# DCDC_RPI.net
KiCad netlist of a schematic drawn in Altium Designer
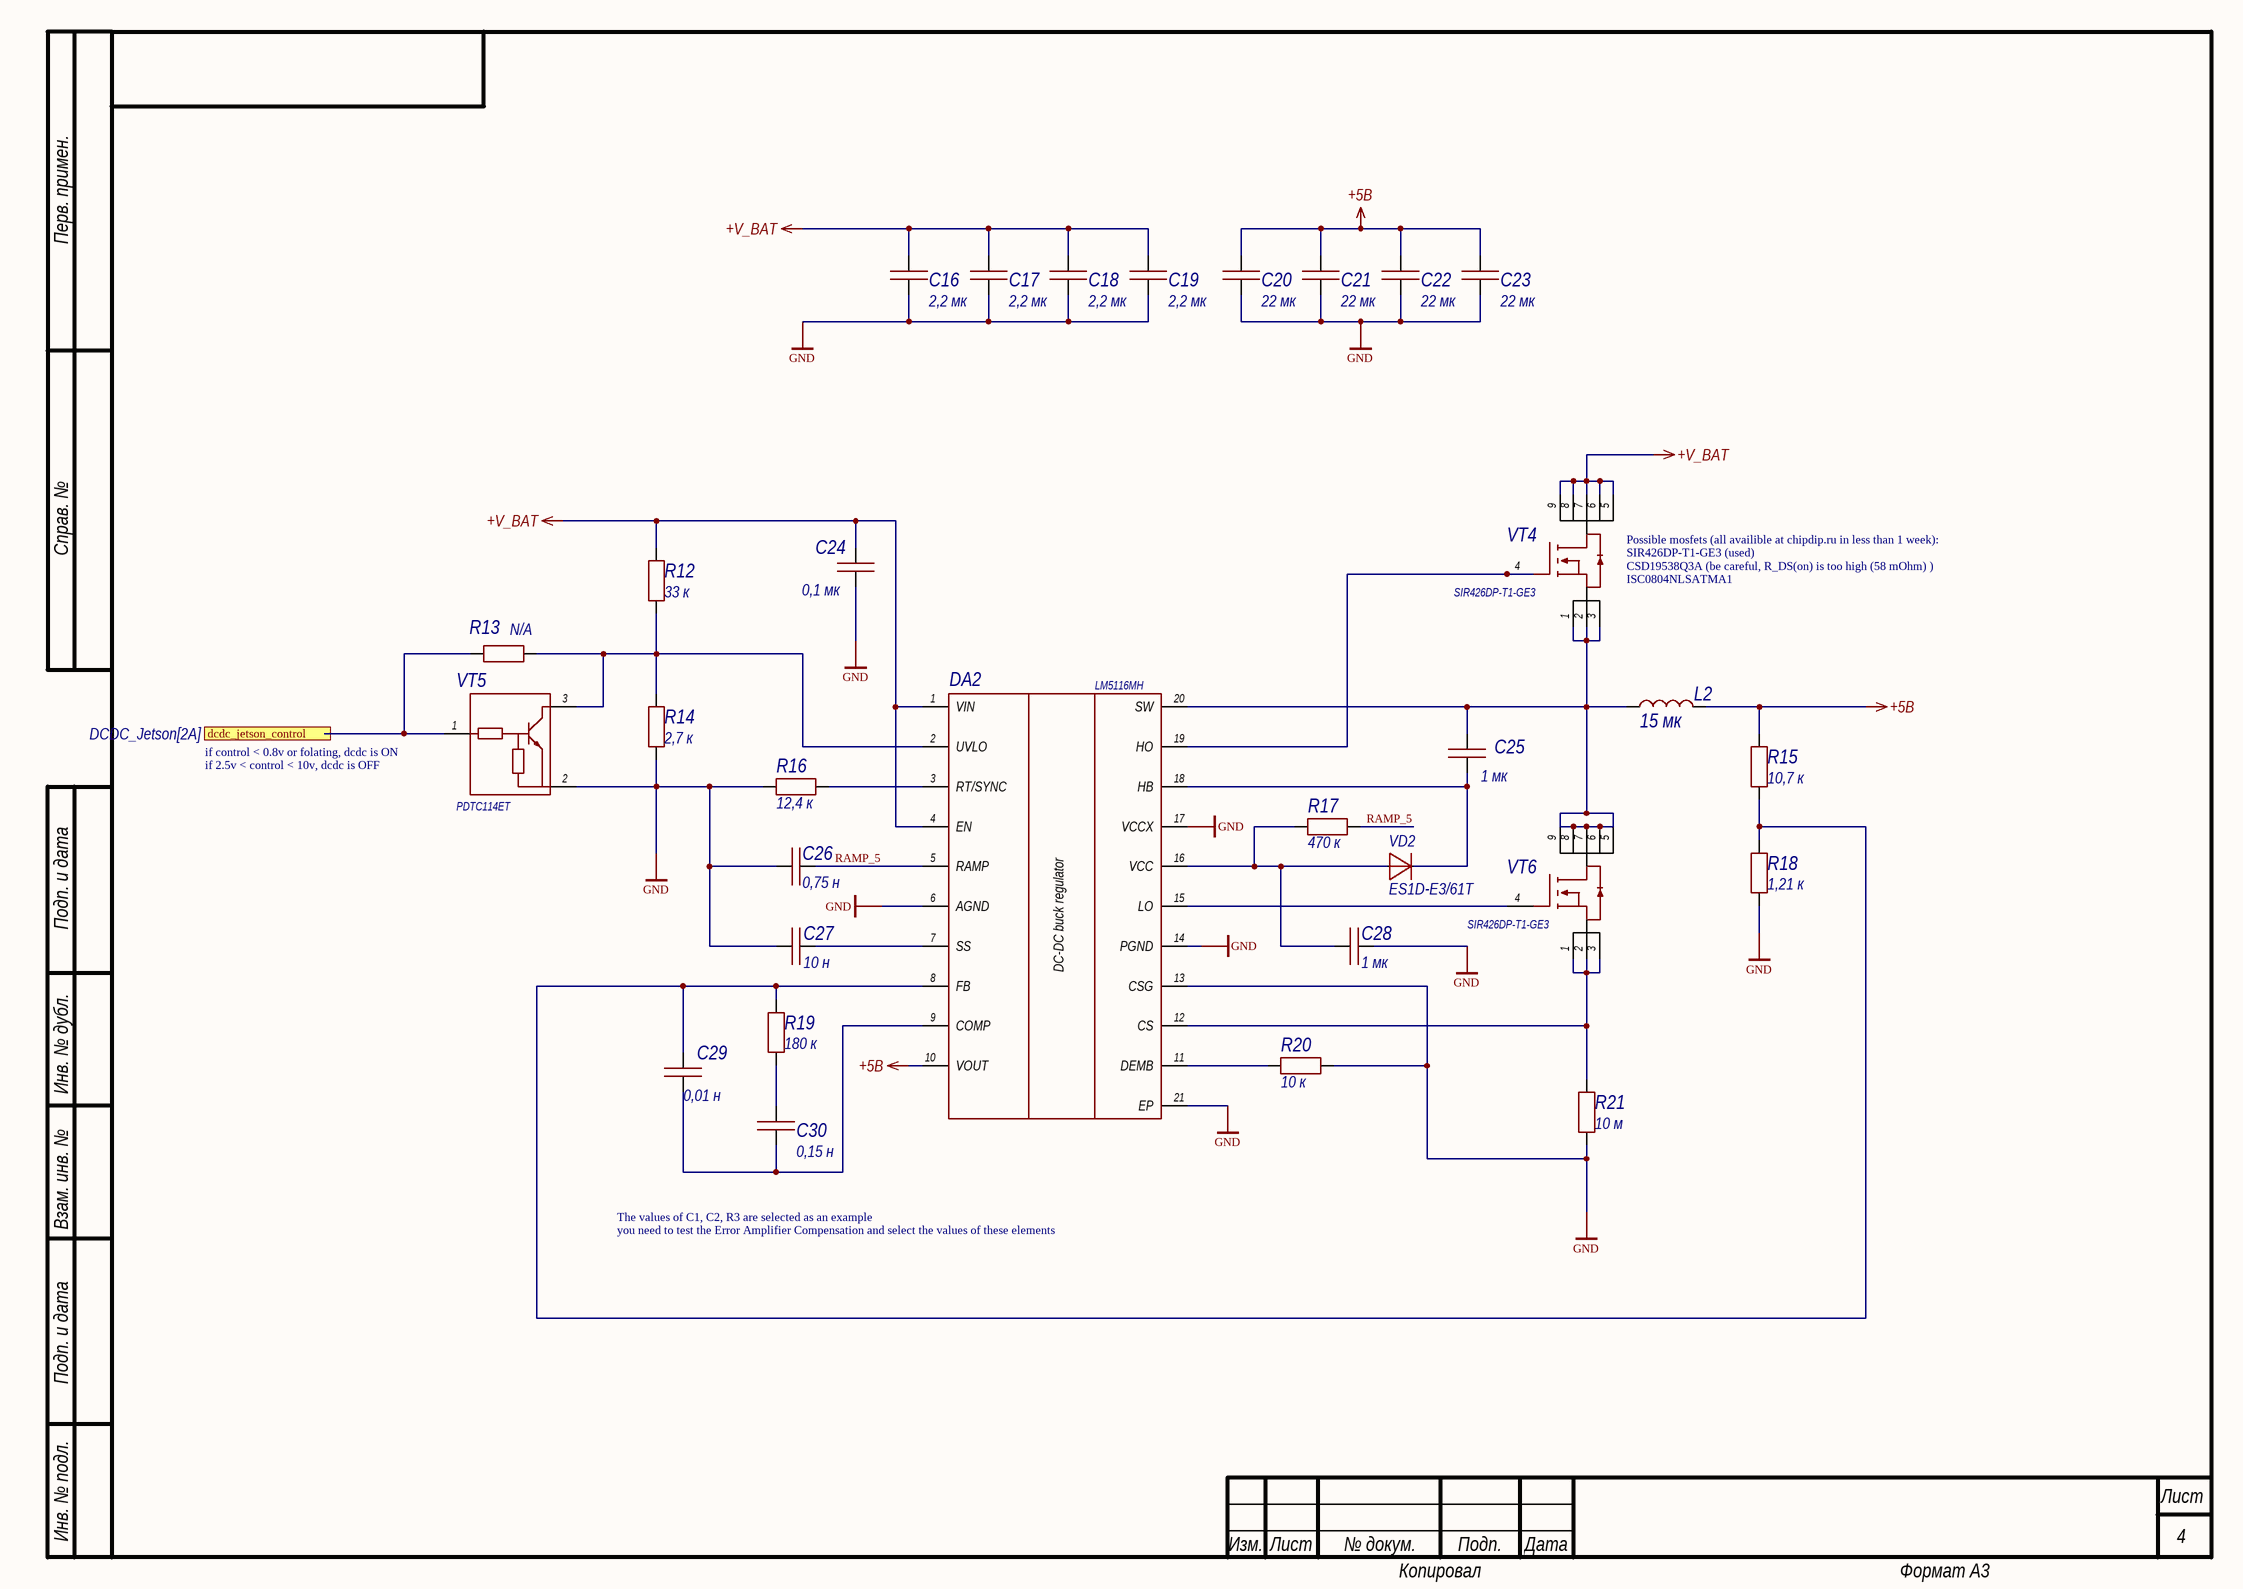
[diagram p0: DCDC_RPI.SchDoc]

(export (version "E")
  (design (tool "Eeschema 10.0.6"))
  (components
    (comp (ref "C16")
      (value "2,2 мк")
      (footprint "1206C")
      (description "Конденсатор")
      (fields (field (name "PART NUMBER") "Capacitor_2,2u_10_50V_X7R_1206C") (field (name "TOLERANCE") "0,1"))
      (libsource (lib "Hydrolib") (part "Capacitor"))
    )
    (comp (ref "C17")
      (value "2,2 мк")
      (footprint "1206C")
      (description "Конденсатор")
      (fields (field (name "PART NUMBER") "Capacitor_2,2u_10_50V_X7R_1206C") (field (name "TOLERANCE") "0,1"))
      (libsource (lib "Hydrolib") (part "Capacitor"))
    )
    (comp (ref "C18")
      (value "2,2 мк")
      (footprint "1206C")
      (description "Конденсатор")
      (fields (field (name "PART NUMBER") "Capacitor_2,2u_10_50V_X7R_1206C") (field (name "TOLERANCE") "0,1"))
      (libsource (lib "Hydrolib") (part "Capacitor"))
    )
    (comp (ref "C19")
      (value "2,2 мк")
      (footprint "1206C")
      (description "Конденсатор")
      (fields (field (name "PART NUMBER") "Capacitor_2,2u_10_50V_X7R_1206C") (field (name "TOLERANCE") "0,1"))
      (libsource (lib "Hydrolib") (part "Capacitor"))
    )
    (comp (ref "C20")
      (value "22 мк")
      (footprint "1210C")
      (description "Конденсатор")
      (fields (field (name "PART NUMBER") "Capacitor_22u_10_25V_X7R_1210C") (field (name "TOLERANCE") "0,1"))
      (libsource (lib "Hydrolib") (part "Capacitor"))
    )
    (comp (ref "C21")
      (value "22 мк")
      (footprint "1210C")
      (description "Конденсатор")
      (fields (field (name "PART NUMBER") "Capacitor_22u_10_25V_X7R_1210C") (field (name "TOLERANCE") "0,1"))
      (libsource (lib "Hydrolib") (part "Capacitor"))
    )
    (comp (ref "C22")
      (value "22 мк")
      (footprint "1210C")
      (description "Конденсатор")
      (fields (field (name "PART NUMBER") "Capacitor_22u_10_25V_X7R_1210C") (field (name "TOLERANCE") "0,1"))
      (libsource (lib "Hydrolib") (part "Capacitor"))
    )
    (comp (ref "C23")
      (value "22 мк")
      (footprint "1210C")
      (description "Конденсатор")
      (fields (field (name "PART NUMBER") "Capacitor_22u_10_25V_X7R_1210C") (field (name "TOLERANCE") "0,1"))
      (libsource (lib "Hydrolib") (part "Capacitor"))
    )
    (comp (ref "C24")
      (value "0,1 мк")
      (footprint "0603C")
      (description "Конденсатор")
      (fields (field (name "PART NUMBER") "Capacitor_0,1u_10_50V_X7R_0603C") (field (name "TOLERANCE") "0,1"))
      (libsource (lib "Hydrolib") (part "Capacitor"))
    )
    (comp (ref "C25")
      (value "1 мк")
      (footprint "0603C")
      (description "Конденсатор")
      (fields (field (name "PART NUMBER") "Capacitor_1u_10_50V_X7R_0603C") (field (name "TOLERANCE") "0,1"))
      (libsource (lib "Hydrolib") (part "Capacitor"))
    )
    (comp (ref "C26")
      (value "0,75 н")
      (footprint "0603C")
      (description "Конденсатор")
      (fields
        (field (name "PART NUMBER") "Capacitor_0,75n_10_50V_X7R_0603C")
        (field (name "TOLERANCE") "0,1")
      )
      (libsource (lib "Hydrolib") (part "Capacitor"))
    )
    (comp (ref "C27")
      (value "10 н")
      (footprint "0603C")
      (description "Конденсатор")
      (fields (field (name "PART NUMBER") "Capacitor_10n_10_50V_X7R_0603C") (field (name "TOLERANCE") "0,1"))
      (libsource (lib "Hydrolib") (part "Capacitor"))
    )
    (comp (ref "C28")
      (value "1 мк")
      (footprint "0603C")
      (description "Конденсатор")
      (fields (field (name "PART NUMBER") "Capacitor_1u_10_50V_X7R_0603C") (field (name "TOLERANCE") "0,1"))
      (libsource (lib "Hydrolib") (part "Capacitor"))
    )
    (comp (ref "C29")
      (value "0,01 н")
      (footprint "0603C")
      (description "Конденсатор")
      (fields
        (field (name "PART NUMBER") "Capacitor_0,01n_10_50V_X7R_0603C")
        (field (name "TOLERANCE") "0,1")
      )
      (libsource (lib "Hydrolib") (part "Capacitor"))
    )
    (comp (ref "C30")
      (value "0,15 н")
      (footprint "0603C")
      (description "Конденсатор")
      (fields
        (field (name "PART NUMBER") "Capacitor_0,15n_10_50V_X7R_0603C")
        (field (name "TOLERANCE") "0,1")
      )
      (libsource (lib "Hydrolib") (part "Capacitor"))
    )
    (comp (ref "DA2")
      (value "LM5116MH")
      (footprint "HTSSOP-20")
      (description "dc-dc понижающий adj 6-100v")
      (fields (field (name "MANUFACTURER_PART_NUMBER") "LM5116MH/NOPB"))
      (libsource (lib "Hydrolib") (part "LM5116MH"))
    )
    (comp (ref "L2")
      (value "15 мк")
      (footprint "SPRH127")
      (description "Индуктивность на 15 мкГн, номинальный ток 8,4 А")
      (fields (field (name "PART NUMBER") "CDSPRH127-150M"))
      (libsource (lib "Hydrolib") (part "Inductance"))
    )
    (comp (ref "R12")
      (value "33 к")
      (footprint "0603R")
      (description "Резистор номиналом 33 кОм и точностью 1%")
      (fields (field (name "PART NUMBER") "Resistor_33k_1_0603") (field (name "TOLERANCE") "1%"))
      (libsource (lib "Hydrolib") (part "Resistor"))
    )
    (comp (ref "R13")
      (value "N/A")
      (footprint "0603R")
      (description "посадочное место 0603 под перемычку")
      (fields (field (name "PART NUMBER") "res_0603_N/A") (field (name "TOLERANCE") "1%"))
      (libsource (lib "") (part "Resistor_1"))
    )
    (comp (ref "R14")
      (value "2,7 к")
      (footprint "0603R")
      (description "Резистор номиналом 2,7 кОм и точностью 1%")
      (fields (field (name "PART NUMBER") "Resistor_2.7k_1_0603") (field (name "TOLERANCE") "1%"))
      (libsource (lib "Hydrolib") (part "Resistor"))
    )
    (comp (ref "R15")
      (value "10,7 к")
      (footprint "0603R")
      (description "Резистор номиналом 10,7 кОм и точностью 1%")
      (fields (field (name "PART NUMBER") "Resistor_10.7k_1_0603") (field (name "TOLERANCE") "1%"))
      (libsource (lib "Hydrolib") (part "Resistor"))
    )
    (comp (ref "R16")
      (value "12,4 к")
      (footprint "0603R")
      (description "Резистор номиналом 12,4 кОм и точностью 1%")
      (fields (field (name "PART NUMBER") "Resistor_12.4k_1_0603") (field (name "TOLERANCE") "1%"))
      (libsource (lib "") (part "Resistor_1"))
    )
    (comp (ref "R17")
      (value "470 к")
      (footprint "0603R")
      (description "Резистор номиналом 470 кОм и точностью 1%")
      (fields (field (name "PART NUMBER") "Resistor_470k_1_0603") (field (name "TOLERANCE") "1%"))
      (libsource (lib "") (part "Resistor_1"))
    )
    (comp (ref "R18")
      (value "1,21 к")
      (footprint "0603R")
      (description "Резистор номиналом 1,21 кОм и точностью 1%")
      (fields (field (name "PART NUMBER") "Resistor_1.21k_1_0603") (field (name "TOLERANCE") "1%"))
      (libsource (lib "Hydrolib") (part "Resistor"))
    )
    (comp (ref "R19")
      (value "180 к")
      (footprint "0603R")
      (description "Резистор номиналом 180 кОм и точностью 1%")
      (fields (field (name "PART NUMBER") "Resistor_180k_1_0603") (field (name "TOLERANCE") "1%"))
      (libsource (lib "Hydrolib") (part "Resistor"))
    )
    (comp (ref "R20")
      (value "10 к")
      (footprint "0603R")
      (description "Резистор номиналом 10 кОм и точностью 1%")
      (fields (field (name "PART NUMBER") "Resistor_10k_1_0603") (field (name "TOLERANCE") "1%"))
      (libsource (lib "") (part "Resistor_1"))
    )
    (comp (ref "R21")
      (value "10 м")
      (footprint "1210R")
      (description "Резистор номиналом 10 мОм, точностью 1%, 0.5Вт")
      (fields (field (name "PART NUMBER") "RL1210FR-070R01L") (field (name "TOLERANCE") "1%"))
      (libsource (lib "Hydrolib") (part "Resistor"))
    )
    (comp (ref "VD2")
      (value "ES1D-E3/61T")
      (footprint "SMA")
      (description "Диод 1A 200V")
      (libsource (lib "Hydrolib") (part "Rectifier_diode"))
    )
    (comp (ref "VT4")
      (value "SIR426DP-T1-GE3")
      (footprint "PowerPAK_SO-8")
      (description "Транзистор полевой MOSFET N-канальный 40В 41.7Вт")
      (libsource (lib "Hydrolib") (part "SIR426DP-T1-GE3"))
    )
    (comp (ref "VT5")
      (value "PDTC114ET")
      (footprint "SOT23-3")
      (description "цифровой npn 50в 100мА")
      (libsource (lib "Hydrolib") (part "PDTC114ET"))
    )
    (comp (ref "VT6")
      (value "SIR426DP-T1-GE3")
      (footprint "PowerPAK_SO-8")
      (description "Транзистор полевой MOSFET N-канальный 40В 41.7Вт")
      (libsource (lib "Hydrolib") (part "SIR426DP-T1-GE3"))
    )
  )
  (nets
    (net (code "1") (name "+5В") (class "Default")
      (node (ref "C20") (pin "2") (pinfunction "2_2") (pintype "passive"))
      (node (ref "C21") (pin "2") (pinfunction "2_2") (pintype "passive"))
      (node (ref "C22") (pin "2") (pinfunction "2_2") (pintype "passive"))
      (node (ref "C23") (pin "2") (pinfunction "2_2") (pintype "passive"))
      (node (ref "DA2") (pin "10") (pinfunction "VOUT_10") (pintype "passive"))
      (node (ref "L2") (pin "2") (pinfunction "2_2") (pintype "passive"))
      (node (ref "R15") (pin "2") (pinfunction "2_2") (pintype "passive"))
    )
    (net (code "2") (name "+V_BAT") (class "Default")
      (node (ref "C16") (pin "2") (pinfunction "2_2") (pintype "passive"))
      (node (ref "C17") (pin "2") (pinfunction "2_2") (pintype "passive"))
      (node (ref "C18") (pin "2") (pinfunction "2_2") (pintype "passive"))
      (node (ref "C19") (pin "2") (pinfunction "2_2") (pintype "passive"))
      (node (ref "C24") (pin "2") (pinfunction "2_2") (pintype "passive"))
      (node (ref "DA2") (pin "1") (pinfunction "VIN_1") (pintype "passive"))
      (node (ref "DA2") (pin "4") (pinfunction "EN_4") (pintype "passive"))
      (node (ref "R12") (pin "2") (pinfunction "2_2") (pintype "passive"))
      (node (ref "VT4") (pin "5") (pinfunction "5_5") (pintype "passive"))
      (node (ref "VT4") (pin "6") (pinfunction "6_6") (pintype "passive"))
      (node (ref "VT4") (pin "7") (pinfunction "7_7") (pintype "passive"))
      (node (ref "VT4") (pin "8") (pinfunction "8_8") (pintype "passive"))
      (node (ref "VT4") (pin "9") (pinfunction "9_9") (pintype "passive"))
    )
    (net (code "3") (name "/RAMP_5") (class "Default")
      (node (ref "C26") (pin "2") (pinfunction "2_2") (pintype "passive"))
      (node (ref "DA2") (pin "5") (pinfunction "RAMP_5") (pintype "passive"))
      (node (ref "R17") (pin "2") (pinfunction "2_2") (pintype "passive"))
    )
    (net (code "4") (name "/dcdc_jetson_control") (class "Default")
      (node (ref "R13") (pin "1") (pinfunction "1_1") (pintype "passive"))
      (node (ref "VT5") (pin "1") (pinfunction "B_1") (pintype "passive"))
    )
    (net (code "5") (name "GND") (class "Default")
      (node (ref "C16") (pin "1") (pinfunction "1_1") (pintype "passive"))
      (node (ref "C17") (pin "1") (pinfunction "1_1") (pintype "passive"))
      (node (ref "C18") (pin "1") (pinfunction "1_1") (pintype "passive"))
      (node (ref "C19") (pin "1") (pinfunction "1_1") (pintype "passive"))
      (node (ref "C20") (pin "1") (pinfunction "1_1") (pintype "passive"))
      (node (ref "C21") (pin "1") (pinfunction "1_1") (pintype "passive"))
      (node (ref "C22") (pin "1") (pinfunction "1_1") (pintype "passive"))
      (node (ref "C23") (pin "1") (pinfunction "1_1") (pintype "passive"))
      (node (ref "C24") (pin "1") (pinfunction "1_1") (pintype "passive"))
      (node (ref "C26") (pin "1") (pinfunction "1_1") (pintype "passive"))
      (node (ref "C27") (pin "1") (pinfunction "1_1") (pintype "passive"))
      (node (ref "C28") (pin "2") (pinfunction "2_2") (pintype "passive"))
      (node (ref "DA2") (pin "13") (pinfunction "CSG_13") (pintype "passive"))
      (node (ref "DA2") (pin "14") (pinfunction "PGND_14") (pintype "passive"))
      (node (ref "DA2") (pin "17") (pinfunction "VCCX_17") (pintype "passive"))
      (node (ref "DA2") (pin "21") (pinfunction "EP_21") (pintype "passive"))
      (node (ref "DA2") (pin "6") (pinfunction "AGND_6") (pintype "passive"))
      (node (ref "R14") (pin "1") (pinfunction "1_1") (pintype "passive"))
      (node (ref "R16") (pin "1") (pinfunction "1_1") (pintype "passive"))
      (node (ref "R18") (pin "1") (pinfunction "1_1") (pintype "passive"))
      (node (ref "R20") (pin "2") (pinfunction "2_2") (pintype "passive"))
      (node (ref "R21") (pin "1") (pinfunction "1_1") (pintype "passive"))
      (node (ref "VT5") (pin "2") (pinfunction "E_2") (pintype "passive"))
    )
    (net (code "6") (name "Net-(C30-Pad2)") (class "Default")
      (node (ref "C30") (pin "2") (pinfunction "2_2") (pintype "passive"))
      (node (ref "R19") (pin "1") (pinfunction "1_1") (pintype "passive"))
    )
    (net (code "7") (name "Net-(DA2-COMP)") (class "Default")
      (node (ref "C29") (pin "1") (pinfunction "1_1") (pintype "passive"))
      (node (ref "C30") (pin "1") (pinfunction "1_1") (pintype "passive"))
      (node (ref "DA2") (pin "9") (pinfunction "COMP_9") (pintype "passive"))
    )
    (net (code "8") (name "Net-(DA2-CS)") (class "Default")
      (node (ref "DA2") (pin "12") (pinfunction "CS_12") (pintype "passive"))
      (node (ref "R21") (pin "2") (pinfunction "2_2") (pintype "passive"))
      (node (ref "VT6") (pin "1") (pinfunction "1_1") (pintype "passive"))
      (node (ref "VT6") (pin "2") (pinfunction "2_2") (pintype "passive"))
      (node (ref "VT6") (pin "3") (pinfunction "3_3") (pintype "passive"))
    )
    (net (code "9") (name "Net-(DA2-DEMB)") (class "Default")
      (node (ref "DA2") (pin "11") (pinfunction "DEMB_11") (pintype "passive"))
      (node (ref "R20") (pin "1") (pinfunction "1_1") (pintype "passive"))
    )
    (net (code "10") (name "Net-(DA2-FB)") (class "Default")
      (node (ref "C29") (pin "2") (pinfunction "2_2") (pintype "passive"))
      (node (ref "DA2") (pin "8") (pinfunction "FB_8") (pintype "passive"))
      (node (ref "R15") (pin "1") (pinfunction "1_1") (pintype "passive"))
      (node (ref "R18") (pin "2") (pinfunction "2_2") (pintype "passive"))
      (node (ref "R19") (pin "2") (pinfunction "2_2") (pintype "passive"))
    )
    (net (code "11") (name "Net-(DA2-HB)") (class "Default")
      (node (ref "C25") (pin "1") (pinfunction "1_1") (pintype "passive"))
      (node (ref "DA2") (pin "18") (pinfunction "HB_18") (pintype "passive"))
      (node (ref "VD2") (pin "2") (pinfunction "2_2") (pintype "passive"))
    )
    (net (code "12") (name "Net-(DA2-HO)") (class "Default")
      (node (ref "DA2") (pin "19") (pinfunction "HO_19") (pintype "passive"))
      (node (ref "VT4") (pin "4") (pinfunction "4_4") (pintype "passive"))
    )
    (net (code "13") (name "Net-(DA2-LO)") (class "Default")
      (node (ref "DA2") (pin "15") (pinfunction "LO_15") (pintype "passive"))
      (node (ref "VT6") (pin "4") (pinfunction "4_4") (pintype "passive"))
    )
    (net (code "14") (name "Net-(DA2-RT{slash}SYNC)") (class "Default")
      (node (ref "DA2") (pin "3") (pinfunction "RT/SYNC_3") (pintype "passive"))
      (node (ref "R16") (pin "2") (pinfunction "2_2") (pintype "passive"))
    )
    (net (code "15") (name "Net-(DA2-SS)") (class "Default")
      (node (ref "C27") (pin "2") (pinfunction "2_2") (pintype "passive"))
      (node (ref "DA2") (pin "7") (pinfunction "SS_7") (pintype "passive"))
    )
    (net (code "16") (name "Net-(DA2-SW)") (class "Default")
      (node (ref "C25") (pin "2") (pinfunction "2_2") (pintype "passive"))
      (node (ref "DA2") (pin "20") (pinfunction "SW_20") (pintype "passive"))
      (node (ref "L2") (pin "1") (pinfunction "1_1") (pintype "passive"))
      (node (ref "VT4") (pin "1") (pinfunction "1_1") (pintype "passive"))
      (node (ref "VT4") (pin "2") (pinfunction "2_2") (pintype "passive"))
      (node (ref "VT4") (pin "3") (pinfunction "3_3") (pintype "passive"))
      (node (ref "VT6") (pin "5") (pinfunction "5_5") (pintype "passive"))
      (node (ref "VT6") (pin "6") (pinfunction "6_6") (pintype "passive"))
      (node (ref "VT6") (pin "7") (pinfunction "7_7") (pintype "passive"))
      (node (ref "VT6") (pin "8") (pinfunction "8_8") (pintype "passive"))
      (node (ref "VT6") (pin "9") (pinfunction "9_9") (pintype "passive"))
    )
    (net (code "17") (name "Net-(DA2-UVLO)") (class "Default")
      (node (ref "DA2") (pin "2") (pinfunction "UVLO_2") (pintype "passive"))
      (node (ref "R12") (pin "1") (pinfunction "1_1") (pintype "passive"))
      (node (ref "R13") (pin "2") (pinfunction "2_2") (pintype "passive"))
      (node (ref "R14") (pin "2") (pinfunction "2_2") (pintype "passive"))
      (node (ref "VT5") (pin "3") (pinfunction "C_3") (pintype "passive"))
    )
    (net (code "18") (name "Net-(DA2-VCC)") (class "Default")
      (node (ref "C28") (pin "1") (pinfunction "1_1") (pintype "passive"))
      (node (ref "DA2") (pin "16") (pinfunction "VCC_16") (pintype "passive"))
      (node (ref "R17") (pin "1") (pinfunction "1_1") (pintype "passive"))
      (node (ref "VD2") (pin "1") (pinfunction "1_1") (pintype "passive"))
    )
  )
)
